# USB-UART.net
KiCad netlist of a schematic drawn in Altium Designer
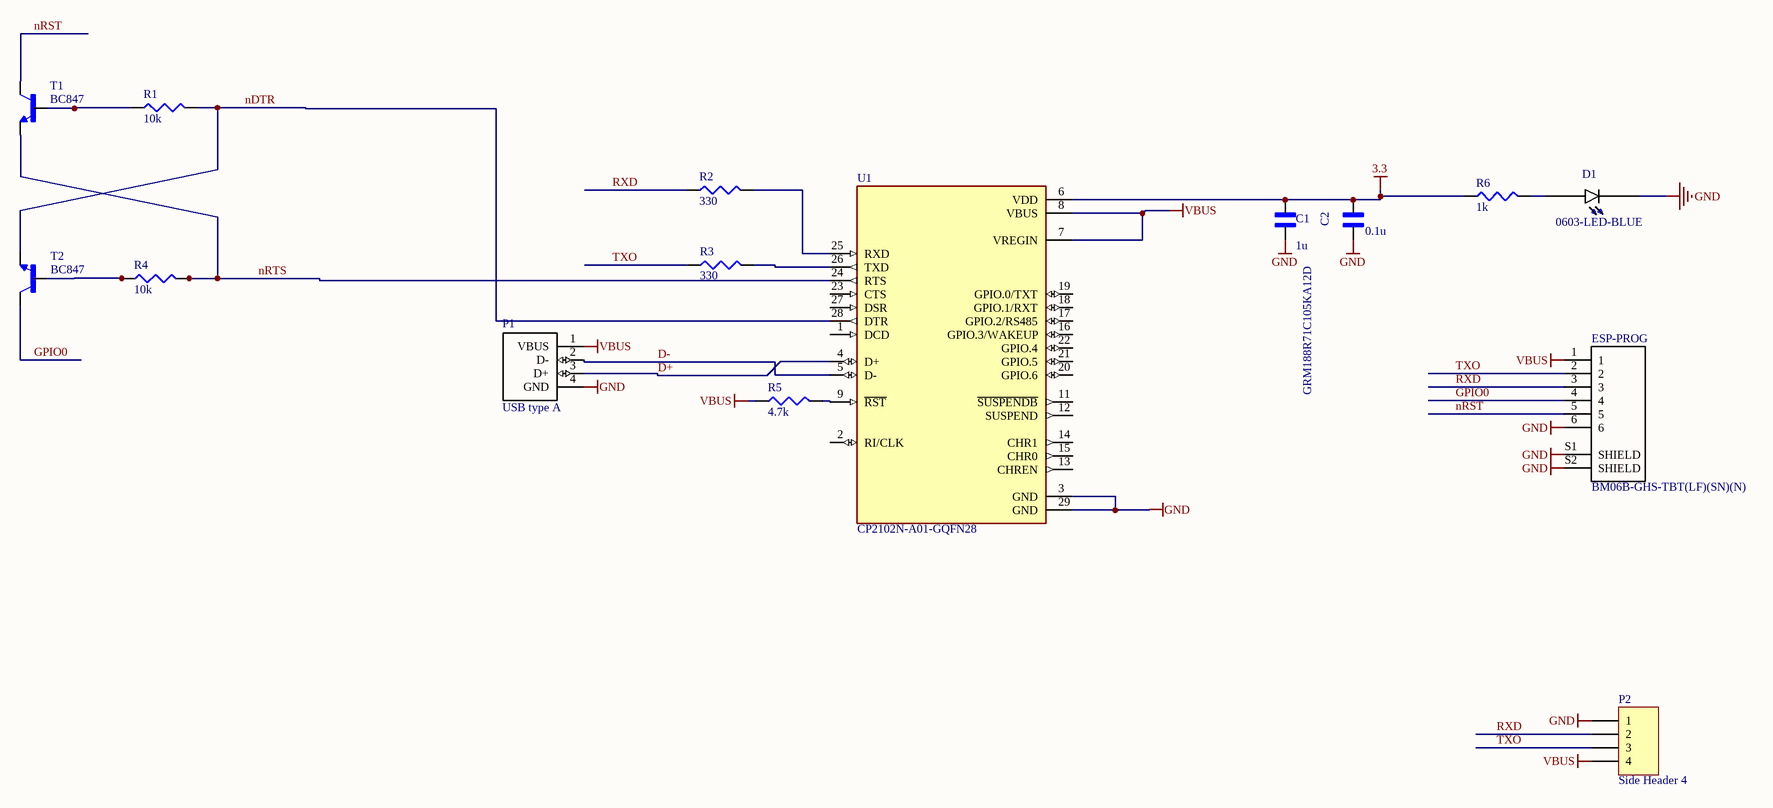
[diagram p0: USB-UART.SchDoc]

(export (version "E")
  (design (tool "Eeschema 10.0.6"))
  (components
    (comp (ref "C1")
      (value "GRM188R71C105KA12D")
      (footprint "CAPC1608X90N")
      (description "SMD Capacitor X7R(EIA) with Capacitance: 1.0uF Tol. 10%. Rated Voltage: 16Vdc")
      (fields (field (name "MF") "Murata Electronics") (field (name "ALTIUM_VALUE") "1u"))
      (libsource (lib "lib") (part "GRM188R71C105KA12D"))
    )
    (comp (ref "C2")
      (value "0.1u")
      (footprint "*CAPC1608X90")
      (description "Cap Thin Film 0.1uf 50v 0603")
      (fields (field (name "MF") "AVX") (field (name "MP") "GX035C104MAT2-500"))
      (libsource (lib "lib") (part "GX035C104MAT2-500"))
    )
    (comp (ref "D1")
      (value "0603-LED-BLUE")
      (footprint "*LEDM1608X80_LTE-C1906R-14(Primary)")
      (description "LED IrLED Chip LED 2-Pin SMD T/R")
      (libsource (lib "lib") (part "LTE-C1906R-14"))
    )
    (comp (ref "ESP-PROG")
      (value "BM06B-GHS-TBT(LF)(SN)(N)")
      (footprint "*JST_BM06B-GHS-TBT(LF)(SN)(N)_BM06B-GHS-TBT(LF)(SN)(N)(Primary)")
      (description "Conn Header Gh Top 6pos 1.25mm")
      (fields (field (name "MP") "BM06B-GHS-TBT_LF__SN__N_") (field (name "MF") "JST Sales"))
      (libsource (lib "lib") (part "BM06B-GHS-TBT(LF)(SN)(N)"))
    )
    (comp (ref "P1")
      (value "USB type A")
      (footprint "USB type A")
      (description "USB - micro A")
      (libsource (lib "lib") (part "USB type A"))
    )
    (comp (ref "P2")
      (value "Side Header 4")
      (footprint "HDR1X4")
      (description "Header, 4-Pin")
      (fields (field (name "MP") "PLS-4R (DS1022-1x4R)"))
      (libsource (lib "lib") (part "Side Header 4"))
    )
    (comp (ref "R1")
      (value "10k")
      (footprint "J1-0603")
      (description "10 kOhms 1 0.1 W 1 10 W Chip Resistor 0603 1608 Metric Thick Film")
      (fields (field (name "MF") "Yageo or NXP") (field (name "MP") "RC0603FR-0710KL"))
      (libsource (lib "lib") (part "RC0603FR-0710KL"))
    )
    (comp (ref "R2")
      (value "330")
      (footprint "J1-0603")
      (description "330 Ohms ±1% 0.1W, 1/10W Chip Resistor 0603 (1608 Metric) Thick Film")
      (fields (field (name "MF") "Yageo or NXP") (field (name "MP") "RC0603FR-07330RL"))
      (libsource (lib "lib") (part "RC0603FR-07330RL"))
    )
    (comp (ref "R3")
      (value "330")
      (footprint "J1-0603")
      (description "330 Ohms ±1% 0.1W, 1/10W Chip Resistor 0603 (1608 Metric) Thick Film")
      (fields (field (name "MF") "Yageo or NXP") (field (name "MP") "RC0603FR-07330RL"))
      (libsource (lib "lib") (part "RC0603FR-07330RL"))
    )
    (comp (ref "R4")
      (value "10k")
      (footprint "J1-0603")
      (description "10 kOhms 1 0.1 W 1 10 W Chip Resistor 0603 1608 Metric Thick Film")
      (fields (field (name "MF") "Yageo or NXP") (field (name "MP") "RC0603FR-0710KL"))
      (libsource (lib "lib") (part "RC0603FR-0710KL"))
    )
    (comp (ref "R5")
      (value "4.7k")
      (footprint "J1-0603")
      (description "4.7 kOhms ±1% 0.1W, 1/10W Chip Resistor 0603 (1608 Metric) Thick Film")
      (fields (field (name "MF") "Yageo or NXP") (field (name "MP") "RC0603FR-074K7L"))
      (libsource (lib "lib") (part "RC0603FR-074K7L"))
    )
    (comp (ref "R6")
      (value "1k")
      (footprint "J1-0603")
      (description "1 kOhms ±1% 0.1W, 1/10W Chip Resistor 0603 (1608 Metric) Moisture Resistant Thick Film")
      (fields (field (name "MF") "Yageo or NXP") (field (name "MP") "RC0603FR-071KL"))
      (libsource (lib "lib") (part "RC0603FR-071KL"))
    )
    (comp (ref "T1")
      (value "BC847")
      (footprint "SOT23")
      (description "<b>NPN TRANSISTOR</b>")
      (fields (field (name "MF") "{'manufacturer': u'Rectron'}"))
      (libsource (lib "") (part "BC847_1"))
    )
    (comp (ref "T2")
      (value "BC847")
      (footprint "SOT23")
      (description "<b>NPN TRANSISTOR</b>")
      (fields (field (name "MF") "{'manufacturer': u'Rectron'}"))
      (libsource (lib "USB-UART") (part "BC847"))
    )
    (comp (ref "U1")
      (value "CP2102N-A01-GQFN28")
      (footprint "QFN50P500X500X80-29N")
      (description "Ic Bridge Usb To Uart 28qfn")
      (fields (field (name "MF") "{'manufacturer': u'Silicon Labs'}"))
      (libsource (lib "USB-UART") (part "CP2102N-A01-GQFN28"))
    )
  )
  (nets
    (net (code "1") (name "/D+") (class "Default")
      (node (ref "P1") (pin "3") (pinfunction "D+_3") (pintype "bidirectional"))
      (node (ref "U1") (pin "4") (pinfunction "D+_4") (pintype "bidirectional"))
    )
    (net (code "2") (name "/D-") (class "Default")
      (node (ref "P1") (pin "2") (pinfunction "D-_2") (pintype "bidirectional"))
      (node (ref "U1") (pin "5") (pinfunction "D-_5") (pintype "bidirectional"))
    )
    (net (code "3") (name "/GPIO0") (class "Default")
      (node (ref "ESP-PROG") (pin "4") (pinfunction "4_4") (pintype "passive"))
      (node (ref "T2") (pin "3") (pinfunction "C_3") (pintype "passive"))
    )
    (net (code "4") (name "/RXD") (class "Default")
      (node (ref "ESP-PROG") (pin "3") (pinfunction "3_3") (pintype "passive"))
      (node (ref "P2") (pin "2") (pinfunction "2_2") (pintype "passive"))
      (node (ref "R2") (pin "1") (pinfunction "1_1") (pintype "passive"))
    )
    (net (code "5") (name "/TXO") (class "Default")
      (node (ref "ESP-PROG") (pin "2") (pinfunction "2_2") (pintype "passive"))
      (node (ref "P2") (pin "3") (pinfunction "3_3") (pintype "passive"))
      (node (ref "R3") (pin "1") (pinfunction "1_1") (pintype "passive"))
    )
    (net (code "6") (name "/nDTR") (class "Default")
      (node (ref "R1") (pin "2") (pinfunction "2_2") (pintype "passive"))
      (node (ref "T2") (pin "2") (pinfunction "E_2") (pintype "passive"))
      (node (ref "U1") (pin "28") (pinfunction "DTR_28") (pintype "output"))
    )
    (net (code "7") (name "/nRST") (class "Default")
      (node (ref "ESP-PROG") (pin "5") (pinfunction "5_5") (pintype "passive"))
      (node (ref "T1") (pin "3") (pinfunction "C_3") (pintype "passive"))
    )
    (net (code "8") (name "/nRTS") (class "Default")
      (node (ref "R4") (pin "2") (pinfunction "2_2") (pintype "passive"))
      (node (ref "T1") (pin "2") (pinfunction "E_2") (pintype "passive"))
      (node (ref "U1") (pin "24") (pinfunction "RTS_24") (pintype "output"))
    )
    (net (code "9") (name "3.3") (class "Default")
      (node (ref "C1") (pin "2") (pinfunction "2_2") (pintype "passive"))
      (node (ref "C2") (pin "1") (pinfunction "1_1") (pintype "passive"))
      (node (ref "R6") (pin "1") (pinfunction "1_1") (pintype "passive"))
      (node (ref "U1") (pin "6") (pinfunction "VDD_6") (pintype "power_in"))
    )
    (net (code "10") (name "GND") (class "Default")
      (node (ref "C1") (pin "1") (pinfunction "1_1") (pintype "passive"))
      (node (ref "C2") (pin "2") (pinfunction "2_2") (pintype "passive"))
      (node (ref "D1") (pin "C") (pinfunction "C_C") (pintype "passive"))
      (node (ref "ESP-PROG") (pin "6") (pinfunction "6_6") (pintype "passive"))
      (node (ref "ESP-PROG") (pin "S1") (pinfunction "SHIELD_S1") (pintype "passive"))
      (node (ref "ESP-PROG") (pin "S2") (pinfunction "SHIELD_S2") (pintype "passive"))
      (node (ref "P1") (pin "4") (pinfunction "GND_4") (pintype "passive"))
      (node (ref "P2") (pin "1") (pinfunction "1_1") (pintype "passive"))
      (node (ref "U1") (pin "29") (pinfunction "GND_29") (pintype "power_in"))
      (node (ref "U1") (pin "3") (pinfunction "GND_3") (pintype "power_in"))
    )
    (net (code "11") (name "Net-(D1-PadA)") (class "Default")
      (node (ref "D1") (pin "A") (pinfunction "A_A") (pintype "passive"))
      (node (ref "R6") (pin "2") (pinfunction "2_2") (pintype "passive"))
    )
    (net (code "12") (name "Net-(T1-B)") (class "Default")
      (node (ref "R1") (pin "1") (pinfunction "1_1") (pintype "passive"))
      (node (ref "T1") (pin "1") (pinfunction "B_1") (pintype "passive"))
    )
    (net (code "13") (name "Net-(T2-B)") (class "Default")
      (node (ref "R4") (pin "1") (pinfunction "1_1") (pintype "passive"))
      (node (ref "T2") (pin "1") (pinfunction "B_1") (pintype "passive"))
    )
    (net (code "14") (name "Net-(U1-RXD)") (class "Default")
      (node (ref "R2") (pin "2") (pinfunction "2_2") (pintype "passive"))
      (node (ref "U1") (pin "25") (pinfunction "RXD_25") (pintype "input"))
    )
    (net (code "15") (name "Net-(U1-TXD)") (class "Default")
      (node (ref "R3") (pin "2") (pinfunction "2_2") (pintype "passive"))
      (node (ref "U1") (pin "26") (pinfunction "TXD_26") (pintype "output"))
    )
    (net (code "16") (name "Net-(U1-~{RST})") (class "Default")
      (node (ref "R5") (pin "2") (pinfunction "2_2") (pintype "passive"))
      (node (ref "U1") (pin "9") (pinfunction "~{RST}_9") (pintype "input"))
    )
    (net (code "17") (name "VBUS") (class "Default")
      (node (ref "ESP-PROG") (pin "1") (pinfunction "1_1") (pintype "passive"))
      (node (ref "P1") (pin "1") (pinfunction "VBUS_1") (pintype "power_in"))
      (node (ref "P2") (pin "4") (pinfunction "4_4") (pintype "passive"))
      (node (ref "R5") (pin "1") (pinfunction "1_1") (pintype "passive"))
      (node (ref "U1") (pin "7") (pinfunction "VREGIN_7") (pintype "power_in"))
      (node (ref "U1") (pin "8") (pinfunction "VBUS_8") (pintype "power_in"))
    )
    (net (code "18") (name "unconnected-(U1-CHR0-Pad15)") (class "Default")
      (node (ref "U1") (pin "15") (pinfunction "CHR0_15") (pintype "output"))
    )
    (net (code "19") (name "unconnected-(U1-CHR1-Pad14)") (class "Default")
      (node (ref "U1") (pin "14") (pinfunction "CHR1_14") (pintype "output"))
    )
    (net (code "20") (name "unconnected-(U1-CHREN-Pad13)") (class "Default")
      (node (ref "U1") (pin "13") (pinfunction "CHREN_13") (pintype "output"))
    )
    (net (code "21") (name "unconnected-(U1-CTS-Pad23)") (class "Default")
      (node (ref "U1") (pin "23") (pinfunction "CTS_23") (pintype "input"))
    )
    (net (code "22") (name "unconnected-(U1-DCD-Pad1)") (class "Default")
      (node (ref "U1") (pin "1") (pinfunction "DCD_1") (pintype "input"))
    )
    (net (code "23") (name "unconnected-(U1-DSR-Pad27)") (class "Default")
      (node (ref "U1") (pin "27") (pinfunction "DSR_27") (pintype "input"))
    )
    (net (code "24") (name "unconnected-(U1-GPIO.0{slash}TXT-Pad19)") (class "Default")
      (node (ref "U1") (pin "19") (pinfunction "GPIO.0/TXT_19") (pintype "bidirectional"))
    )
    (net (code "25") (name "unconnected-(U1-GPIO.1{slash}RXT-Pad18)") (class "Default")
      (node (ref "U1") (pin "18") (pinfunction "GPIO.1/RXT_18") (pintype "bidirectional"))
    )
    (net (code "26") (name "unconnected-(U1-GPIO.2{slash}RS485-Pad17)") (class "Default")
      (node (ref "U1") (pin "17") (pinfunction "GPIO.2/RS485_17") (pintype "bidirectional"))
    )
    (net (code "27") (name "unconnected-(U1-GPIO.3{slash}WAKEUP-Pad16)") (class "Default")
      (node (ref "U1") (pin "16") (pinfunction "GPIO.3/WAKEUP_16") (pintype "bidirectional"))
    )
    (net (code "28") (name "unconnected-(U1-GPIO.4-Pad22)") (class "Default")
      (node (ref "U1") (pin "22") (pinfunction "GPIO.4_22") (pintype "bidirectional"))
    )
    (net (code "29") (name "unconnected-(U1-GPIO.5-Pad21)") (class "Default")
      (node (ref "U1") (pin "21") (pinfunction "GPIO.5_21") (pintype "bidirectional"))
    )
    (net (code "30") (name "unconnected-(U1-GPIO.6-Pad20)") (class "Default")
      (node (ref "U1") (pin "20") (pinfunction "GPIO.6_20") (pintype "bidirectional"))
    )
    (net (code "31") (name "unconnected-(U1-RI{slash}CLK-Pad2)") (class "Default")
      (node (ref "U1") (pin "2") (pinfunction "RI/CLK_2") (pintype "bidirectional"))
    )
    (net (code "32") (name "unconnected-(U1-SUSPEND-Pad12)") (class "Default")
      (node (ref "U1") (pin "12") (pinfunction "SUSPEND_12") (pintype "output"))
    )
    (net (code "33") (name "unconnected-(U1-~{SUSPENDB}-Pad11)") (class "Default")
      (node (ref "U1") (pin "11") (pinfunction "~{SUSPENDB}_11") (pintype "output"))
    )
  )
)
